# DSPA.net
KiCad netlist of a schematic drawn in Altium Designer
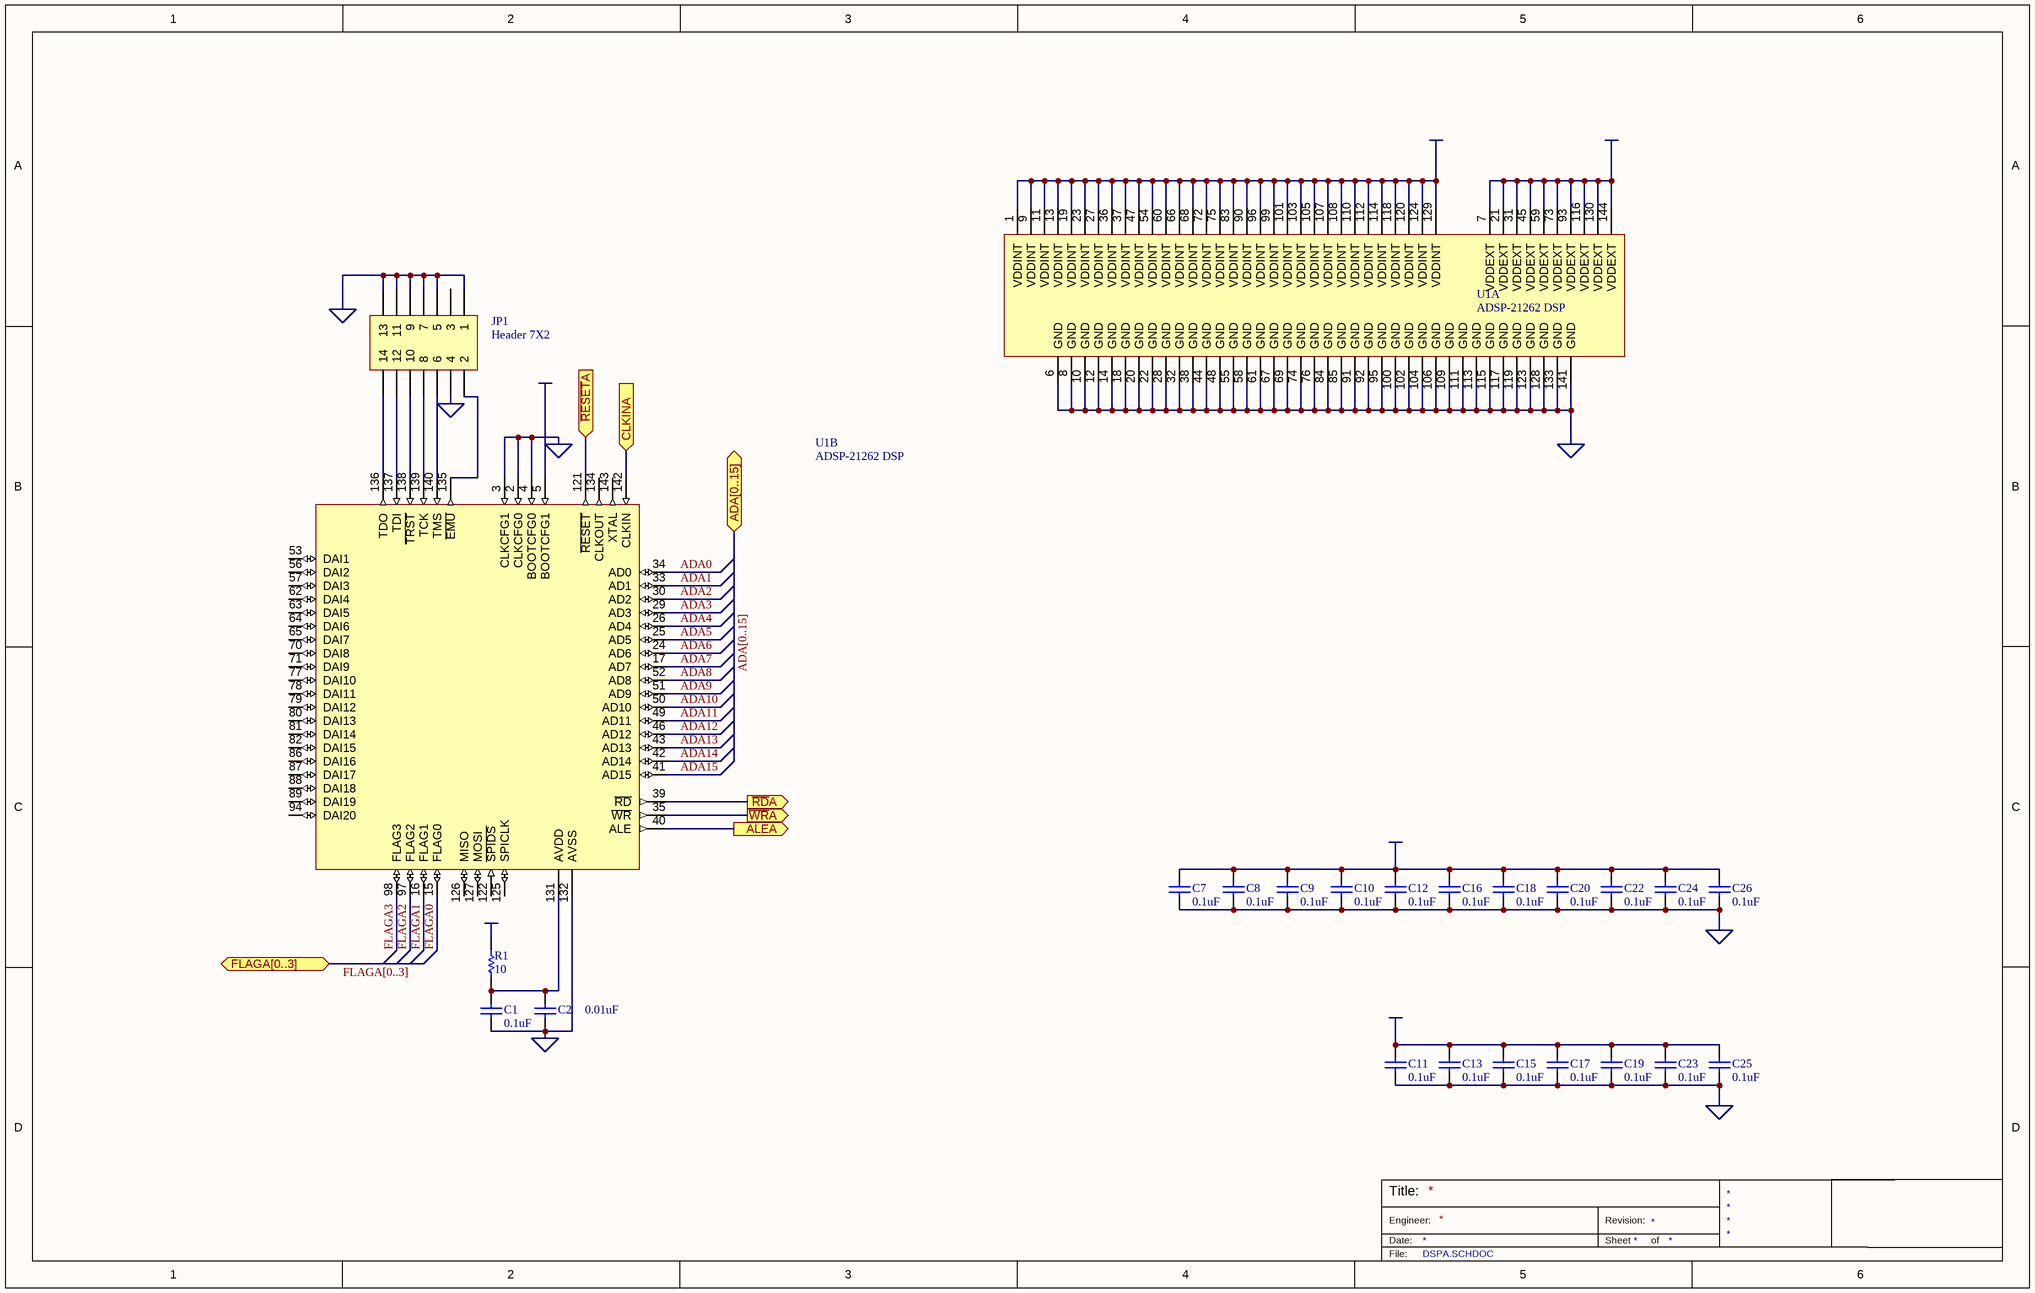
[diagram p0: DSPA.SCHDOC]

(export (version "E")
  (design (tool "Eeschema 10.0.6"))
  (components
    (comp (ref "C1")
      (value "0.1uF")
      (footprint "CC1005-0402")
      (description "Capacitor")
      (fields
        (field (name "MANUFACTURER") "Generic Components")
        (field (name "Comment") "Cap")
        (field (name "PUBLISHER") "Altium Limited")
      )
      (libsource (lib "Miscellaneous Devices") (part "Cap"))
    )
    (comp (ref "C2")
      (value "0.01uF")
      (footprint "CC1005-0402")
      (description "Capacitor")
      (fields
        (field (name "MANUFACTURER") "Generic Components")
        (field (name "Comment") "Cap")
        (field (name "PUBLISHER") "Altium Limited")
      )
      (libsource (lib "Miscellaneous Devices") (part "Cap"))
    )
    (comp (ref "C7")
      (value "0.1uF")
      (footprint "CC1005-0402")
      (description "Capacitor")
      (fields
        (field (name "MANUFACTURER") "Generic Components")
        (field (name "Comment") "Cap")
        (field (name "PUBLISHER") "Altium Limited")
      )
      (libsource (lib "Miscellaneous Devices") (part "Cap"))
    )
    (comp (ref "C8")
      (value "0.1uF")
      (footprint "CC1005-0402")
      (description "Capacitor")
      (fields
        (field (name "MANUFACTURER") "Generic Components")
        (field (name "Comment") "Cap")
        (field (name "PUBLISHER") "Altium Limited")
      )
      (libsource (lib "Miscellaneous Devices") (part "Cap"))
    )
    (comp (ref "C9")
      (value "0.1uF")
      (footprint "CC1005-0402")
      (description "Capacitor")
      (fields
        (field (name "MANUFACTURER") "Generic Components")
        (field (name "Comment") "Cap")
        (field (name "PUBLISHER") "Altium Limited")
      )
      (libsource (lib "Miscellaneous Devices") (part "Cap"))
    )
    (comp (ref "C10")
      (value "0.1uF")
      (footprint "CC1005-0402")
      (description "Capacitor")
      (fields
        (field (name "MANUFACTURER") "Generic Components")
        (field (name "Comment") "Cap")
        (field (name "PUBLISHER") "Altium Limited")
      )
      (libsource (lib "Miscellaneous Devices") (part "Cap"))
    )
    (comp (ref "C11")
      (value "0.1uF")
      (footprint "CC1005-0402")
      (description "Capacitor")
      (fields
        (field (name "MANUFACTURER") "Generic Components")
        (field (name "Comment") "Cap")
        (field (name "PUBLISHER") "Altium Limited")
      )
      (libsource (lib "Miscellaneous Devices") (part "Cap"))
    )
    (comp (ref "C12")
      (value "0.1uF")
      (footprint "CC1005-0402")
      (description "Capacitor")
      (fields
        (field (name "MANUFACTURER") "Generic Components")
        (field (name "Comment") "Cap")
        (field (name "PUBLISHER") "Altium Limited")
      )
      (libsource (lib "Miscellaneous Devices") (part "Cap"))
    )
    (comp (ref "C13")
      (value "0.1uF")
      (footprint "CC1005-0402")
      (description "Capacitor")
      (fields
        (field (name "MANUFACTURER") "Generic Components")
        (field (name "Comment") "Cap")
        (field (name "PUBLISHER") "Altium Limited")
      )
      (libsource (lib "Miscellaneous Devices") (part "Cap"))
    )
    (comp (ref "C15")
      (value "0.1uF")
      (footprint "CC1005-0402")
      (description "Capacitor")
      (fields
        (field (name "MANUFACTURER") "Generic Components")
        (field (name "Comment") "Cap")
        (field (name "PUBLISHER") "Altium Limited")
      )
      (libsource (lib "Miscellaneous Devices") (part "Cap"))
    )
    (comp (ref "C16")
      (value "0.1uF")
      (footprint "CC1005-0402")
      (description "Capacitor")
      (fields
        (field (name "MANUFACTURER") "Generic Components")
        (field (name "Comment") "Cap")
        (field (name "PUBLISHER") "Altium Limited")
      )
      (libsource (lib "Miscellaneous Devices") (part "Cap"))
    )
    (comp (ref "C17")
      (value "0.1uF")
      (footprint "CC1005-0402")
      (description "Capacitor")
      (fields
        (field (name "MANUFACTURER") "Generic Components")
        (field (name "Comment") "Cap")
        (field (name "PUBLISHER") "Altium Limited")
      )
      (libsource (lib "Miscellaneous Devices") (part "Cap"))
    )
    (comp (ref "C18")
      (value "0.1uF")
      (footprint "CC1005-0402")
      (description "Capacitor")
      (fields
        (field (name "MANUFACTURER") "Generic Components")
        (field (name "Comment") "Cap")
        (field (name "PUBLISHER") "Altium Limited")
      )
      (libsource (lib "Miscellaneous Devices") (part "Cap"))
    )
    (comp (ref "C19")
      (value "0.1uF")
      (footprint "CC1005-0402")
      (description "Capacitor")
      (fields
        (field (name "MANUFACTURER") "Generic Components")
        (field (name "Comment") "Cap")
        (field (name "PUBLISHER") "Altium Limited")
      )
      (libsource (lib "Miscellaneous Devices") (part "Cap"))
    )
    (comp (ref "C20")
      (value "0.1uF")
      (footprint "CC1005-0402")
      (description "Capacitor")
      (fields
        (field (name "MANUFACTURER") "Generic Components")
        (field (name "Comment") "Cap")
        (field (name "PUBLISHER") "Altium Limited")
      )
      (libsource (lib "Miscellaneous Devices") (part "Cap"))
    )
    (comp (ref "C22")
      (value "0.1uF")
      (footprint "CC1005-0402")
      (description "Capacitor")
      (fields
        (field (name "MANUFACTURER") "Generic Components")
        (field (name "Comment") "Cap")
        (field (name "PUBLISHER") "Altium Limited")
      )
      (libsource (lib "Miscellaneous Devices") (part "Cap"))
    )
    (comp (ref "C23")
      (value "0.1uF")
      (footprint "CC1005-0402")
      (description "Capacitor")
      (fields
        (field (name "MANUFACTURER") "Generic Components")
        (field (name "Comment") "Cap")
        (field (name "PUBLISHER") "Altium Limited")
      )
      (libsource (lib "Miscellaneous Devices") (part "Cap"))
    )
    (comp (ref "C24")
      (value "0.1uF")
      (footprint "CC1005-0402")
      (description "Capacitor")
      (fields
        (field (name "MANUFACTURER") "Generic Components")
        (field (name "Comment") "Cap")
        (field (name "PUBLISHER") "Altium Limited")
      )
      (libsource (lib "Miscellaneous Devices") (part "Cap"))
    )
    (comp (ref "C25")
      (value "0.1uF")
      (footprint "CC1005-0402")
      (description "Capacitor")
      (fields
        (field (name "MANUFACTURER") "Generic Components")
        (field (name "Comment") "Cap")
        (field (name "PUBLISHER") "Altium Limited")
      )
      (libsource (lib "Miscellaneous Devices") (part "Cap"))
    )
    (comp (ref "C26")
      (value "0.1uF")
      (footprint "CC1005-0402")
      (description "Capacitor")
      (fields
        (field (name "MANUFACTURER") "Generic Components")
        (field (name "Comment") "Cap")
        (field (name "PUBLISHER") "Altium Limited")
      )
      (libsource (lib "Miscellaneous Devices") (part "Cap"))
    )
    (comp (ref "JP1")
      (value "Header 7X2")
      (footprint "HDR2X7")
      (description "Header, 7-Pin, Dual row")
      (fields (field (name "MANUFACTURER") "Generic Components") (field (name "PUBLISHER") "Altium Limited"))
      (libsource (lib "Miscellaneous Connectors") (part "Header 7X2"))
    )
    (comp (ref "R1")
      (value "10")
      (footprint "CR1608-0603")
      (description "Resistor")
      (fields
        (field (name "MANUFACTURER") "Generic Components")
        (field (name "Comment") "Res1")
        (field (name "PUBLISHER") "Altium Limited")
      )
      (libsource (lib "Miscellaneous Devices") (part "Res1"))
    )
    (comp (ref "U1")
      (value "ADSP-21262 DSP")
      (footprint "F-QFP20X20-G144/N")
      (description "SHARC 200 MHz 32-bit floating-point SIMD DSP")
      (libsource (lib "parts") (part "ADSP-21262"))
    )
  )
  (nets
    (net (code "1") (name "+1.2VCC") (class "Default")
      (node (ref "C10") (pin "2") (pinfunction "2_2") (pintype "passive"))
      (node (ref "C12") (pin "2") (pinfunction "2_2") (pintype "passive"))
      (node (ref "C16") (pin "2") (pinfunction "2_2") (pintype "passive"))
      (node (ref "C18") (pin "2") (pinfunction "2_2") (pintype "passive"))
      (node (ref "C20") (pin "2") (pinfunction "2_2") (pintype "passive"))
      (node (ref "C22") (pin "2") (pinfunction "2_2") (pintype "passive"))
      (node (ref "C24") (pin "2") (pinfunction "2_2") (pintype "passive"))
      (node (ref "C26") (pin "2") (pinfunction "2_2") (pintype "passive"))
      (node (ref "C7") (pin "2") (pinfunction "2_2") (pintype "passive"))
      (node (ref "C8") (pin "2") (pinfunction "2_2") (pintype "passive"))
      (node (ref "C9") (pin "2") (pinfunction "2_2") (pintype "passive"))
      (node (ref "R1") (pin "1") (pinfunction "1_1") (pintype "passive"))
      (node (ref "U1") (pin "1") (pinfunction "VDDINT_1") (pintype "power_in"))
      (node (ref "U1") (pin "101") (pinfunction "VDDINT_101") (pintype "power_in"))
      (node (ref "U1") (pin "103") (pinfunction "VDDINT_103") (pintype "power_in"))
      (node (ref "U1") (pin "105") (pinfunction "VDDINT_105") (pintype "power_in"))
      (node (ref "U1") (pin "107") (pinfunction "VDDINT_107") (pintype "power_in"))
      (node (ref "U1") (pin "108") (pinfunction "VDDINT_108") (pintype "power_in"))
      (node (ref "U1") (pin "11") (pinfunction "VDDINT_11") (pintype "power_in"))
      (node (ref "U1") (pin "110") (pinfunction "VDDINT_110") (pintype "power_in"))
      (node (ref "U1") (pin "112") (pinfunction "VDDINT_112") (pintype "power_in"))
      (node (ref "U1") (pin "114") (pinfunction "VDDINT_114") (pintype "power_in"))
      (node (ref "U1") (pin "118") (pinfunction "VDDINT_118") (pintype "power_in"))
      (node (ref "U1") (pin "120") (pinfunction "VDDINT_120") (pintype "power_in"))
      (node (ref "U1") (pin "124") (pinfunction "VDDINT_124") (pintype "power_in"))
      (node (ref "U1") (pin "129") (pinfunction "VDDINT_129") (pintype "power_in"))
      (node (ref "U1") (pin "13") (pinfunction "VDDINT_13") (pintype "power_in"))
      (node (ref "U1") (pin "19") (pinfunction "VDDINT_19") (pintype "power_in"))
      (node (ref "U1") (pin "23") (pinfunction "VDDINT_23") (pintype "power_in"))
      (node (ref "U1") (pin "27") (pinfunction "VDDINT_27") (pintype "power_in"))
      (node (ref "U1") (pin "36") (pinfunction "VDDINT_36") (pintype "power_in"))
      (node (ref "U1") (pin "37") (pinfunction "VDDINT_37") (pintype "power_in"))
      (node (ref "U1") (pin "47") (pinfunction "VDDINT_47") (pintype "power_in"))
      (node (ref "U1") (pin "54") (pinfunction "VDDINT_54") (pintype "power_in"))
      (node (ref "U1") (pin "60") (pinfunction "VDDINT_60") (pintype "power_in"))
      (node (ref "U1") (pin "66") (pinfunction "VDDINT_66") (pintype "power_in"))
      (node (ref "U1") (pin "68") (pinfunction "VDDINT_68") (pintype "power_in"))
      (node (ref "U1") (pin "72") (pinfunction "VDDINT_72") (pintype "power_in"))
      (node (ref "U1") (pin "75") (pinfunction "VDDINT_75") (pintype "power_in"))
      (node (ref "U1") (pin "83") (pinfunction "VDDINT_83") (pintype "power_in"))
      (node (ref "U1") (pin "9") (pinfunction "VDDINT_9") (pintype "power_in"))
      (node (ref "U1") (pin "90") (pinfunction "VDDINT_90") (pintype "power_in"))
      (node (ref "U1") (pin "96") (pinfunction "VDDINT_96") (pintype "power_in"))
      (node (ref "U1") (pin "99") (pinfunction "VDDINT_99") (pintype "power_in"))
    )
    (net (code "2") (name "/ADA0") (class "Default")
      (node (ref "U1") (pin "34") (pinfunction "AD0_34") (pintype "bidirectional"))
    )
    (net (code "3") (name "/ADA1") (class "Default")
      (node (ref "U1") (pin "33") (pinfunction "AD1_33") (pintype "bidirectional"))
    )
    (net (code "4") (name "/ADA2") (class "Default")
      (node (ref "U1") (pin "30") (pinfunction "AD2_30") (pintype "bidirectional"))
    )
    (net (code "5") (name "/ADA3") (class "Default")
      (node (ref "U1") (pin "29") (pinfunction "AD3_29") (pintype "bidirectional"))
    )
    (net (code "6") (name "/ADA4") (class "Default")
      (node (ref "U1") (pin "26") (pinfunction "AD4_26") (pintype "bidirectional"))
    )
    (net (code "7") (name "/ADA5") (class "Default")
      (node (ref "U1") (pin "25") (pinfunction "AD5_25") (pintype "bidirectional"))
    )
    (net (code "8") (name "/ADA6") (class "Default")
      (node (ref "U1") (pin "24") (pinfunction "AD6_24") (pintype "bidirectional"))
    )
    (net (code "9") (name "/ADA7") (class "Default")
      (node (ref "U1") (pin "17") (pinfunction "AD7_17") (pintype "bidirectional"))
    )
    (net (code "10") (name "/ADA8") (class "Default")
      (node (ref "U1") (pin "52") (pinfunction "AD8_52") (pintype "bidirectional"))
    )
    (net (code "11") (name "/ADA9") (class "Default")
      (node (ref "U1") (pin "51") (pinfunction "AD9_51") (pintype "bidirectional"))
    )
    (net (code "12") (name "/ADA10") (class "Default")
      (node (ref "U1") (pin "50") (pinfunction "AD10_50") (pintype "bidirectional"))
    )
    (net (code "13") (name "/ADA11") (class "Default")
      (node (ref "U1") (pin "49") (pinfunction "AD11_49") (pintype "bidirectional"))
    )
    (net (code "14") (name "/ADA12") (class "Default")
      (node (ref "U1") (pin "46") (pinfunction "AD12_46") (pintype "bidirectional"))
    )
    (net (code "15") (name "/ADA13") (class "Default")
      (node (ref "U1") (pin "43") (pinfunction "AD13_43") (pintype "bidirectional"))
    )
    (net (code "16") (name "/ADA14") (class "Default")
      (node (ref "U1") (pin "42") (pinfunction "AD14_42") (pintype "bidirectional"))
    )
    (net (code "17") (name "/ADA15") (class "Default")
      (node (ref "U1") (pin "41") (pinfunction "AD15_41") (pintype "bidirectional"))
    )
    (net (code "19") (name "/ALEA") (class "Default")
      (node (ref "U1") (pin "40") (pinfunction "ALE_40") (pintype "output"))
    )
    (net (code "20") (name "/CLKINA") (class "Default")
      (node (ref "U1") (pin "142") (pinfunction "CLKIN_142") (pintype "input"))
    )
    (net (code "21") (name "/FLAGA0") (class "Default")
      (node (ref "U1") (pin "15") (pinfunction "FLAG0_15") (pintype "bidirectional"))
    )
    (net (code "22") (name "/FLAGA1") (class "Default")
      (node (ref "U1") (pin "16") (pinfunction "FLAG1_16") (pintype "bidirectional"))
    )
    (net (code "23") (name "/FLAGA2") (class "Default")
      (node (ref "U1") (pin "97") (pinfunction "FLAG2_97") (pintype "bidirectional"))
    )
    (net (code "24") (name "/FLAGA3") (class "Default")
      (node (ref "U1") (pin "98") (pinfunction "FLAG3_98") (pintype "bidirectional"))
    )
    (net (code "26") (name "/~{RD}A") (class "Default")
      (node (ref "U1") (pin "39") (pinfunction "~{RD}_39") (pintype "output"))
    )
    (net (code "27") (name "/~{RESET}A") (class "Default")
      (node (ref "U1") (pin "121") (pinfunction "~{RESET}_121") (pintype "output"))
    )
    (net (code "28") (name "/~{WR}A") (class "Default")
      (node (ref "U1") (pin "35") (pinfunction "~{WR}_35") (pintype "output"))
    )
    (net (code "29") (name "GND") (class "Default")
      (node (ref "C1") (pin "1") (pinfunction "1_1") (pintype "passive"))
      (node (ref "C10") (pin "1") (pinfunction "1_1") (pintype "passive"))
      (node (ref "C11") (pin "1") (pinfunction "1_1") (pintype "passive"))
      (node (ref "C12") (pin "1") (pinfunction "1_1") (pintype "passive"))
      (node (ref "C13") (pin "1") (pinfunction "1_1") (pintype "passive"))
      (node (ref "C15") (pin "1") (pinfunction "1_1") (pintype "passive"))
      (node (ref "C16") (pin "1") (pinfunction "1_1") (pintype "passive"))
      (node (ref "C17") (pin "1") (pinfunction "1_1") (pintype "passive"))
      (node (ref "C18") (pin "1") (pinfunction "1_1") (pintype "passive"))
      (node (ref "C19") (pin "1") (pinfunction "1_1") (pintype "passive"))
      (node (ref "C2") (pin "1") (pinfunction "1_1") (pintype "passive"))
      (node (ref "C20") (pin "1") (pinfunction "1_1") (pintype "passive"))
      (node (ref "C22") (pin "1") (pinfunction "1_1") (pintype "passive"))
      (node (ref "C23") (pin "1") (pinfunction "1_1") (pintype "passive"))
      (node (ref "C24") (pin "1") (pinfunction "1_1") (pintype "passive"))
      (node (ref "C25") (pin "1") (pinfunction "1_1") (pintype "passive"))
      (node (ref "C26") (pin "1") (pinfunction "1_1") (pintype "passive"))
      (node (ref "C7") (pin "1") (pinfunction "1_1") (pintype "passive"))
      (node (ref "C8") (pin "1") (pinfunction "1_1") (pintype "passive"))
      (node (ref "C9") (pin "1") (pinfunction "1_1") (pintype "passive"))
      (node (ref "JP1") (pin "1") (pinfunction "1_1") (pintype "passive"))
      (node (ref "JP1") (pin "11") (pinfunction "11_11") (pintype "passive"))
      (node (ref "JP1") (pin "13") (pinfunction "13_13") (pintype "passive"))
      (node (ref "JP1") (pin "4") (pinfunction "4_4") (pintype "passive"))
      (node (ref "JP1") (pin "5") (pinfunction "5_5") (pintype "passive"))
      (node (ref "JP1") (pin "7") (pinfunction "7_7") (pintype "passive"))
      (node (ref "JP1") (pin "9") (pinfunction "9_9") (pintype "passive"))
      (node (ref "U1") (pin "10") (pinfunction "GND_10") (pintype "power_in"))
      (node (ref "U1") (pin "100") (pinfunction "GND_100") (pintype "power_in"))
      (node (ref "U1") (pin "102") (pinfunction "GND_102") (pintype "power_in"))
      (node (ref "U1") (pin "104") (pinfunction "GND_104") (pintype "power_in"))
      (node (ref "U1") (pin "106") (pinfunction "GND_106") (pintype "power_in"))
      (node (ref "U1") (pin "109") (pinfunction "GND_109") (pintype "power_in"))
      (node (ref "U1") (pin "111") (pinfunction "GND_111") (pintype "power_in"))
      (node (ref "U1") (pin "113") (pinfunction "GND_113") (pintype "power_in"))
      (node (ref "U1") (pin "115") (pinfunction "GND_115") (pintype "power_in"))
      (node (ref "U1") (pin "117") (pinfunction "GND_117") (pintype "power_in"))
      (node (ref "U1") (pin "119") (pinfunction "GND_119") (pintype "power_in"))
      (node (ref "U1") (pin "12") (pinfunction "GND_12") (pintype "power_in"))
      (node (ref "U1") (pin "123") (pinfunction "GND_123") (pintype "power_in"))
      (node (ref "U1") (pin "128") (pinfunction "GND_128") (pintype "power_in"))
      (node (ref "U1") (pin "132") (pinfunction "AVSS_132") (pintype "power_in"))
      (node (ref "U1") (pin "133") (pinfunction "GND_133") (pintype "power_in"))
      (node (ref "U1") (pin "14") (pinfunction "GND_14") (pintype "power_in"))
      (node (ref "U1") (pin "141") (pinfunction "GND_141") (pintype "power_in"))
      (node (ref "U1") (pin "18") (pinfunction "GND_18") (pintype "power_in"))
      (node (ref "U1") (pin "2") (pinfunction "CLKCFG0_2") (pintype "input"))
      (node (ref "U1") (pin "20") (pinfunction "GND_20") (pintype "power_in"))
      (node (ref "U1") (pin "22") (pinfunction "GND_22") (pintype "power_in"))
      (node (ref "U1") (pin "28") (pinfunction "GND_28") (pintype "power_in"))
      (node (ref "U1") (pin "3") (pinfunction "CLKCFG1_3") (pintype "input"))
      (node (ref "U1") (pin "32") (pinfunction "GND_32") (pintype "power_in"))
      (node (ref "U1") (pin "38") (pinfunction "GND_38") (pintype "power_in"))
      (node (ref "U1") (pin "4") (pinfunction "BOOTCFG0_4") (pintype "input"))
      (node (ref "U1") (pin "44") (pinfunction "GND_44") (pintype "power_in"))
      (node (ref "U1") (pin "48") (pinfunction "GND_48") (pintype "power_in"))
      (node (ref "U1") (pin "55") (pinfunction "GND_55") (pintype "power_in"))
      (node (ref "U1") (pin "58") (pinfunction "GND_58") (pintype "power_in"))
      (node (ref "U1") (pin "6") (pinfunction "GND_6") (pintype "power_in"))
      (node (ref "U1") (pin "61") (pinfunction "GND_61") (pintype "power_in"))
      (node (ref "U1") (pin "67") (pinfunction "GND_67") (pintype "power_in"))
      (node (ref "U1") (pin "69") (pinfunction "GND_69") (pintype "power_in"))
      (node (ref "U1") (pin "74") (pinfunction "GND_74") (pintype "power_in"))
      (node (ref "U1") (pin "76") (pinfunction "GND_76") (pintype "power_in"))
      (node (ref "U1") (pin "8") (pinfunction "GND_8") (pintype "power_in"))
      (node (ref "U1") (pin "84") (pinfunction "GND_84") (pintype "power_in"))
      (node (ref "U1") (pin "85") (pinfunction "GND_85") (pintype "power_in"))
      (node (ref "U1") (pin "91") (pinfunction "GND_91") (pintype "power_in"))
      (node (ref "U1") (pin "92") (pinfunction "GND_92") (pintype "power_in"))
      (node (ref "U1") (pin "95") (pinfunction "GND_95") (pintype "power_in"))
    )
    (net (code "30") (name "Net-(U1B-AVDD)") (class "Default")
      (node (ref "C1") (pin "2") (pinfunction "2_2") (pintype "passive"))
      (node (ref "C2") (pin "2") (pinfunction "2_2") (pintype "passive"))
      (node (ref "R1") (pin "2") (pinfunction "2_2") (pintype "passive"))
      (node (ref "U1") (pin "131") (pinfunction "AVDD_131") (pintype "power_in"))
    )
    (net (code "31") (name "Net-(U1B-TCK)") (class "Default")
      (node (ref "JP1") (pin "8") (pinfunction "8_8") (pintype "passive"))
      (node (ref "U1") (pin "139") (pinfunction "TCK_139") (pintype "input"))
    )
    (net (code "32") (name "Net-(U1B-TDI)") (class "Default")
      (node (ref "JP1") (pin "12") (pinfunction "12_12") (pintype "passive"))
      (node (ref "U1") (pin "137") (pinfunction "TDI_137") (pintype "input"))
    )
    (net (code "33") (name "Net-(U1B-TDO)") (class "Default")
      (node (ref "JP1") (pin "14") (pinfunction "14_14") (pintype "passive"))
      (node (ref "U1") (pin "136") (pinfunction "TDO_136") (pintype "output"))
    )
    (net (code "34") (name "Net-(U1B-TMS)") (class "Default")
      (node (ref "JP1") (pin "6") (pinfunction "6_6") (pintype "passive"))
      (node (ref "U1") (pin "140") (pinfunction "TMS_140") (pintype "input"))
    )
    (net (code "35") (name "Net-(U1B-~{EMU})") (class "Default")
      (node (ref "JP1") (pin "2") (pinfunction "2_2") (pintype "passive"))
      (node (ref "U1") (pin "135") (pinfunction "~{EMU}_135") (pintype "output"))
    )
    (net (code "36") (name "Net-(U1B-~{TRST})") (class "Default")
      (node (ref "JP1") (pin "10") (pinfunction "10_10") (pintype "passive"))
      (node (ref "U1") (pin "138") (pinfunction "~{TRST}_138") (pintype "input"))
    )
    (net (code "37") (name "VCC") (class "Default")
      (node (ref "C11") (pin "2") (pinfunction "2_2") (pintype "passive"))
      (node (ref "C13") (pin "2") (pinfunction "2_2") (pintype "passive"))
      (node (ref "C15") (pin "2") (pinfunction "2_2") (pintype "passive"))
      (node (ref "C17") (pin "2") (pinfunction "2_2") (pintype "passive"))
      (node (ref "C19") (pin "2") (pinfunction "2_2") (pintype "passive"))
      (node (ref "C23") (pin "2") (pinfunction "2_2") (pintype "passive"))
      (node (ref "C25") (pin "2") (pinfunction "2_2") (pintype "passive"))
      (node (ref "U1") (pin "116") (pinfunction "VDDEXT_116") (pintype "power_in"))
      (node (ref "U1") (pin "130") (pinfunction "VDDEXT_130") (pintype "power_in"))
      (node (ref "U1") (pin "144") (pinfunction "VDDEXT_144") (pintype "power_in"))
      (node (ref "U1") (pin "21") (pinfunction "VDDEXT_21") (pintype "power_in"))
      (node (ref "U1") (pin "31") (pinfunction "VDDEXT_31") (pintype "power_in"))
      (node (ref "U1") (pin "45") (pinfunction "VDDEXT_45") (pintype "power_in"))
      (node (ref "U1") (pin "5") (pinfunction "BOOTCFG1_5") (pintype "input"))
      (node (ref "U1") (pin "59") (pinfunction "VDDEXT_59") (pintype "power_in"))
      (node (ref "U1") (pin "7") (pinfunction "VDDEXT_7") (pintype "power_in"))
      (node (ref "U1") (pin "73") (pinfunction "VDDEXT_73") (pintype "power_in"))
      (node (ref "U1") (pin "93") (pinfunction "VDDEXT_93") (pintype "power_in"))
    )
    (net (code "38") (name "unconnected-(JP1-Pad3)") (class "Default")
      (node (ref "JP1") (pin "3") (pinfunction "3_3") (pintype "passive"))
    )
    (net (code "39") (name "unconnected-(U1B-CLKOUT-Pad134)") (class "Default")
      (node (ref "U1") (pin "134") (pinfunction "CLKOUT_134") (pintype "output"))
    )
    (net (code "40") (name "unconnected-(U1B-DAI1-Pad53)") (class "Default")
      (node (ref "U1") (pin "53") (pinfunction "DAI1_53") (pintype "bidirectional"))
    )
    (net (code "41") (name "unconnected-(U1B-DAI2-Pad56)") (class "Default")
      (node (ref "U1") (pin "56") (pinfunction "DAI2_56") (pintype "bidirectional"))
    )
    (net (code "42") (name "unconnected-(U1B-DAI3-Pad57)") (class "Default")
      (node (ref "U1") (pin "57") (pinfunction "DAI3_57") (pintype "bidirectional"))
    )
    (net (code "43") (name "unconnected-(U1B-DAI4-Pad62)") (class "Default")
      (node (ref "U1") (pin "62") (pinfunction "DAI4_62") (pintype "bidirectional"))
    )
    (net (code "44") (name "unconnected-(U1B-DAI5-Pad63)") (class "Default")
      (node (ref "U1") (pin "63") (pinfunction "DAI5_63") (pintype "bidirectional"))
    )
    (net (code "45") (name "unconnected-(U1B-DAI6-Pad64)") (class "Default")
      (node (ref "U1") (pin "64") (pinfunction "DAI6_64") (pintype "bidirectional"))
    )
    (net (code "46") (name "unconnected-(U1B-DAI7-Pad65)") (class "Default")
      (node (ref "U1") (pin "65") (pinfunction "DAI7_65") (pintype "bidirectional"))
    )
    (net (code "47") (name "unconnected-(U1B-DAI8-Pad70)") (class "Default")
      (node (ref "U1") (pin "70") (pinfunction "DAI8_70") (pintype "bidirectional"))
    )
    (net (code "48") (name "unconnected-(U1B-DAI9-Pad71)") (class "Default")
      (node (ref "U1") (pin "71") (pinfunction "DAI9_71") (pintype "bidirectional"))
    )
    (net (code "49") (name "unconnected-(U1B-DAI10-Pad77)") (class "Default")
      (node (ref "U1") (pin "77") (pinfunction "DAI10_77") (pintype "bidirectional"))
    )
    (net (code "50") (name "unconnected-(U1B-DAI11-Pad78)") (class "Default")
      (node (ref "U1") (pin "78") (pinfunction "DAI11_78") (pintype "bidirectional"))
    )
    (net (code "51") (name "unconnected-(U1B-DAI12-Pad79)") (class "Default")
      (node (ref "U1") (pin "79") (pinfunction "DAI12_79") (pintype "bidirectional"))
    )
    (net (code "52") (name "unconnected-(U1B-DAI13-Pad80)") (class "Default")
      (node (ref "U1") (pin "80") (pinfunction "DAI13_80") (pintype "bidirectional"))
    )
    (net (code "53") (name "unconnected-(U1B-DAI14-Pad81)") (class "Default")
      (node (ref "U1") (pin "81") (pinfunction "DAI14_81") (pintype "bidirectional"))
    )
    (net (code "54") (name "unconnected-(U1B-DAI15-Pad82)") (class "Default")
      (node (ref "U1") (pin "82") (pinfunction "DAI15_82") (pintype "bidirectional"))
    )
    (net (code "55") (name "unconnected-(U1B-DAI16-Pad86)") (class "Default")
      (node (ref "U1") (pin "86") (pinfunction "DAI16_86") (pintype "bidirectional"))
    )
    (net (code "56") (name "unconnected-(U1B-DAI17-Pad87)") (class "Default")
      (node (ref "U1") (pin "87") (pinfunction "DAI17_87") (pintype "bidirectional"))
    )
    (net (code "57") (name "unconnected-(U1B-DAI18-Pad88)") (class "Default")
      (node (ref "U1") (pin "88") (pinfunction "DAI18_88") (pintype "bidirectional"))
    )
    (net (code "58") (name "unconnected-(U1B-DAI19-Pad89)") (class "Default")
      (node (ref "U1") (pin "89") (pinfunction "DAI19_89") (pintype "bidirectional"))
    )
    (net (code "59") (name "unconnected-(U1B-DAI20-Pad94)") (class "Default")
      (node (ref "U1") (pin "94") (pinfunction "DAI20_94") (pintype "bidirectional"))
    )
    (net (code "60") (name "unconnected-(U1B-MISO-Pad126)") (class "Default")
      (node (ref "U1") (pin "126") (pinfunction "MISO_126") (pintype "bidirectional"))
    )
    (net (code "61") (name "unconnected-(U1B-MOSI-Pad127)") (class "Default")
      (node (ref "U1") (pin "127") (pinfunction "MOSI_127") (pintype "bidirectional"))
    )
    (net (code "62") (name "unconnected-(U1B-SPICLK-Pad125)") (class "Default")
      (node (ref "U1") (pin "125") (pinfunction "SPICLK_125") (pintype "bidirectional"))
    )
    (net (code "63") (name "unconnected-(U1B-XTAL-Pad143)") (class "Default")
      (node (ref "U1") (pin "143") (pinfunction "XTAL_143") (pintype "output"))
    )
    (net (code "64") (name "unconnected-(U1B-~{SPIDS}-Pad122)") (class "Default")
      (node (ref "U1") (pin "122") (pinfunction "~{SPIDS}_122") (pintype "input"))
    )
  )
)
